# SY_HR08_MCU_POWER_V1_1.net
KiCad netlist of a schematic drawn in Altium Designer
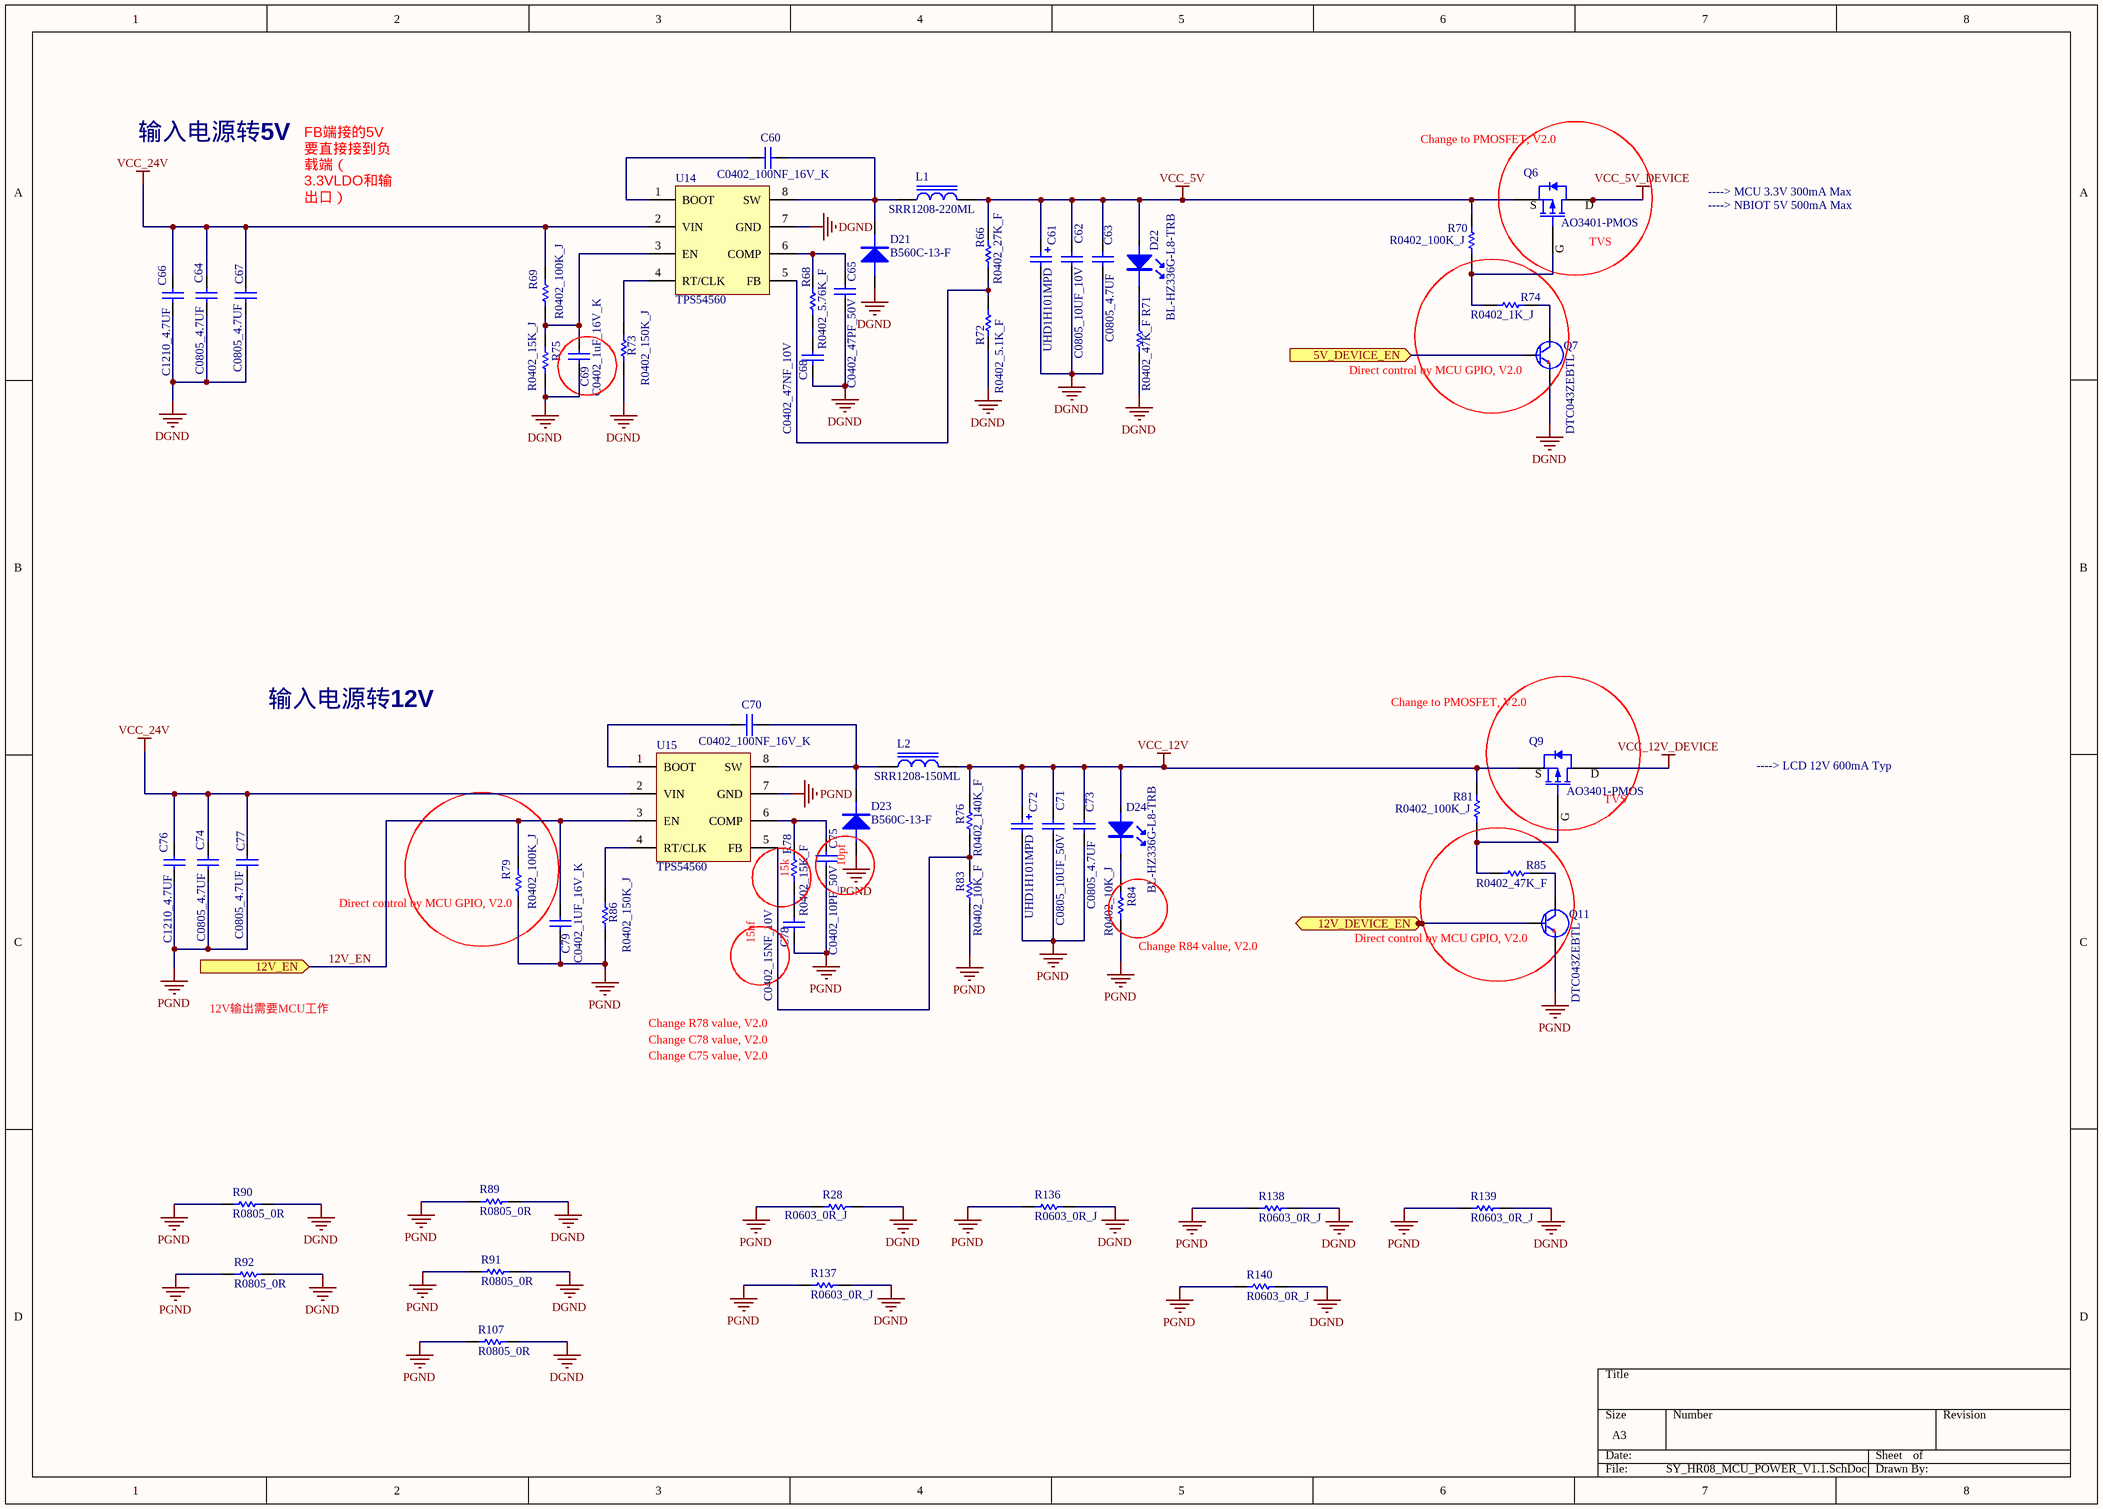
[diagram p0: SY_HR08_MCU_POWER_V1.1.SchDoc]

(export (version "E")
  (design (tool "Eeschema 10.0.6"))
  (components
    (comp (ref "C60")
      (value "C0402_100NF_16V_K")
      (footprint "CAP0402_HQ")
      (description "电容_100nF_0402_X7R_16V_K")
      (libsource (lib "zhangky_sch") (part "C0402_100NF_16V_K"))
    )
    (comp (ref "C61")
      (value "UHD1H101MPD")
      (footprint "UHD1H101MPD")
      (description "铝电解电容_100uF_80115_50V_20%")
      (fields (field (name "MANUFACTURER") "nichicon"))
      (libsource (lib "zhangky_sch") (part "UHD1H101MPD"))
    )
    (comp (ref "C62")
      (value "C0805_10UF_10V")
      (footprint "CAP0805-B")
      (description "电容_10uF_0805_X5R_10V_K")
      (libsource (lib "zhangky_sch") (part "C0805_10UF_10V"))
    )
    (comp (ref "C63")
      (value "C0805_4.7UF")
      (footprint "CAP0805")
      (description "电容_4.7uF_0805_X5R_50V_K")
      (libsource (lib "zhangky_sch") (part "C0805_4.7UF"))
    )
    (comp (ref "C64")
      (value "C0805_4.7UF")
      (footprint "CAP0805")
      (description "电容_4.7uF_0805_X5R_50V_K")
      (libsource (lib "zhangky_sch") (part "C0805_4.7UF"))
    )
    (comp (ref "C65")
      (value "C0402_47PF_50V")
      (footprint "CAP0402_HQ")
      (description "电容47pF(0402-COG-50V-J)")
      (libsource (lib "zhangky_sch") (part "C0402_47PF_50V"))
    )
    (comp (ref "C66")
      (value "C1210_4.7UF")
      (footprint "C1210")
      (description "电容_4.7uF_1210_X7R_50V_K")
      (libsource (lib "zhangky_sch") (part "C1210_4.7UF"))
    )
    (comp (ref "C67")
      (value "C0805_4.7UF")
      (footprint "CAP0805")
      (description "电容_4.7uF_0805_X5R_50V_K")
      (libsource (lib "zhangky_sch") (part "C0805_4.7UF"))
    )
    (comp (ref "C68")
      (value "C0402_47NF_10V")
      (footprint "CAP0402_HQ")
      (description "电容47nF(0402-X7R-10V-K)")
      (libsource (lib "zhangky_sch") (part "C0402_47NF_10V"))
    )
    (comp (ref "C69")
      (value "C0402_1uF_16V_K")
      (footprint "CAP0402_HQ")
      (description "电容_100nF_0402_X7R_16V_K")
      (libsource (lib "zhangky_sch") (part "C0402_100NF_16V_K"))
    )
    (comp (ref "C70")
      (value "C0402_100NF_16V_K")
      (footprint "CAP0402_HQ")
      (description "电容_100nF_0402_X7R_16V_K")
      (libsource (lib "zhangky_sch") (part "C0402_100NF_16V_K"))
    )
    (comp (ref "C71")
      (value "C0805_10UF_50V")
      (footprint "CAP0805-B")
      (description "电容_10uF_0805_X5R_10V_K")
      (libsource (lib "zhangky_sch") (part "C0805_10UF_10V"))
    )
    (comp (ref "C72")
      (value "UHD1H101MPD")
      (footprint "UHD1H101MPD")
      (description "铝电解电容_100uF_80115_50V_20%")
      (fields (field (name "MANUFACTURER") "nichicon"))
      (libsource (lib "zhangky_sch") (part "UHD1H101MPD"))
    )
    (comp (ref "C73")
      (value "C0805_4.7UF")
      (footprint "CAP0805")
      (description "电容_4.7uF_0805_X5R_50V_K")
      (libsource (lib "zhangky_sch") (part "C0805_4.7UF"))
    )
    (comp (ref "C74")
      (value "C0805_4.7UF")
      (footprint "CAP0805")
      (description "电容_4.7uF_0805_X5R_50V_K")
      (libsource (lib "zhangky_sch") (part "C0805_4.7UF"))
    )
    (comp (ref "C75")
      (value "C0402_10PF_50V")
      (footprint "CAP0402_HQ")
      (description "电容47pF(0402-COG-50V-J)")
      (libsource (lib "zhangky_sch") (part "C0402_47PF_50V"))
    )
    (comp (ref "C76")
      (value "C1210_4.7UF")
      (footprint "C1210")
      (description "电容_4.7uF_1210_X7R_50V_K")
      (libsource (lib "zhangky_sch") (part "C1210_4.7UF"))
    )
    (comp (ref "C77")
      (value "C0805_4.7UF")
      (footprint "CAP0805")
      (description "电容_4.7uF_0805_X5R_50V_K")
      (libsource (lib "zhangky_sch") (part "C0805_4.7UF"))
    )
    (comp (ref "C78")
      (value "C0402_15NF_10V")
      (footprint "CAP0402_HQ")
      (description "电容47nF(0402-X7R-10V-K)")
      (libsource (lib "zhangky_sch") (part "C0402_47NF_10V"))
    )
    (comp (ref "C79")
      (value "C0402_1UF_16V_K")
      (footprint "CAP0402_HQ")
      (description "电容_100nF_0402_X7R_16V_K")
      (libsource (lib "zhangky_sch") (part "C0402_100NF_16V_K"))
    )
    (comp (ref "D21")
      (value "B560C-13-F")
      (footprint "B540C-13-F")
      (description "肖特基二极管_5A_SMC")
      (libsource (lib "zhangky_sch") (part "B560C-13-F"))
    )
    (comp (ref "D22")
      (value "BL-HZ336G-L8-TRB")
      (footprint "LED_1.6_0.8_0.4")
      (description "LED_(白色_0603_2.8V)_(HUE仅收5-5,5-6,5-7的标示，CAE仅收含P的标示)")
      (fields (field (name "MANUFACTURER") "Bright(佰鸿)"))
      (libsource (lib "zhangky_sch") (part "BL-HZ336G-L8-TRB"))
    )
    (comp (ref "D23")
      (value "B560C-13-F")
      (footprint "B540C-13-F")
      (description "肖特基二极管_5A_SMC")
      (libsource (lib "zhangky_sch") (part "B560C-13-F"))
    )
    (comp (ref "D24")
      (value "BL-HZ336G-L8-TRB")
      (footprint "LED_1.6_0.8_0.4")
      (description "LED_(白色_0603_2.8V)_(HUE仅收5-5,5-6,5-7的标示，CAE仅收含P的标示)")
      (fields (field (name "MANUFACTURER") "Bright(佰鸿)"))
      (libsource (lib "zhangky_sch") (part "BL-HZ336G-L8-TRB"))
    )
    (comp (ref "L1")
      (value "SRR1208-220ML")
      (footprint "SRR1208")
      (description "功率电感_22uH_12.7*12.7*8.5mm_4A(Irat )_3.5A(Irms)_20%")
      (libsource (lib "zhangky_sch") (part "SRR1208-220ML"))
    )
    (comp (ref "L2")
      (value "SRR1208-150ML")
      (footprint "SRR1208")
      (description "功率电感_15uH_12.7*12.7*8.5mm_4A(Irat )_3.5A(Irms)_20%")
      (libsource (lib "zhangky_sch") (part "SRR1208-150ML"))
    )
    (comp (ref "Q6")
      (value "AO3401-PMOS")
      (footprint "AO3400")
      (libsource (lib "zhangky_sch") (part "AO3401-PMOS"))
    )
    (comp (ref "Q7")
      (value "DTC043ZEBTL")
      (footprint "DTC043ZEBTL$2F$$2F$DTC143ZE$2F$$2F$LDTC143ZET1G")
      (description "NPN三极管_100mA_EMT3F")
      (libsource (lib "zhangky_sch") (part "DTC043ZEBTL"))
    )
    (comp (ref "Q9")
      (value "AO3401-PMOS")
      (footprint "AO3400")
      (libsource (lib "zhangky_sch") (part "AO3401-PMOS"))
    )
    (comp (ref "Q11")
      (value "DTC043ZEBTL")
      (footprint "DTC043ZEBTL$2F$$2F$DTC143ZE$2F$$2F$LDTC143ZET1G")
      (description "NPN三极管_100mA_EMT3F")
      (libsource (lib "zhangky_sch") (part "DTC043ZEBTL"))
    )
    (comp (ref "R28")
      (value "R0603_0R_J")
      (footprint "RES0603-A")
      (description "电阻0R(0603-0.1W-J)")
      (libsource (lib "zhangky_sch") (part "R0603_0R_J"))
    )
    (comp (ref "R66")
      (value "R0402_27K_F")
      (footprint "RES0402_HQ")
      (description "电阻_27K_0402_1/16W_F")
      (libsource (lib "zhangky_sch") (part "R0402_27K_F"))
    )
    (comp (ref "R68")
      (value "R0402_5.76K_F")
      (footprint "RES0402_HQ")
      (description "电阻_5.76K_0402_1/16W_F")
      (libsource (lib "zhangky_sch") (part "R0402_5.76K_F"))
    )
    (comp (ref "R69")
      (value "R0402_100K_J")
      (footprint "RES0402_HQ")
      (description "电阻100K(0402-0.0625W-J)")
      (libsource (lib "zhangky_sch") (part "R0402_100K_J"))
    )
    (comp (ref "R70")
      (value "R0402_100K_J")
      (footprint "RES0402_HQ")
      (description "电阻100K(0402-0.0625W-J)")
      (libsource (lib "zhangky_sch") (part "R0402_100K_J"))
    )
    (comp (ref "R71")
      (value "R0402_47K_F")
      (footprint "RES0402_HQ")
      (description "电阻10K(0402-0.0625W-J)")
      (libsource (lib "zhangky_sch") (part "R0402_10K_J"))
    )
    (comp (ref "R72")
      (value "R0402_5.1K_F")
      (footprint "RES0402_HQ")
      (description "电阻5.1K(0402-0.0625W-J)")
      (libsource (lib "zhangky_sch") (part "R0402_5.1K_F"))
    )
    (comp (ref "R73")
      (value "R0402_150K_J")
      (footprint "RES0402_HQ")
      (description "电阻150K(0402-0.0625w-J)")
      (libsource (lib "zhangky_sch") (part "R0402_150K_J"))
    )
    (comp (ref "R74")
      (value "R0402_1K_J")
      (footprint "RES0402_HQ")
      (description "电阻100K(0402-0.0625W-J)")
      (libsource (lib "zhangky_sch") (part "R0402_100K_J"))
    )
    (comp (ref "R75")
      (value "R0402_15K_J")
      (footprint "RES0402_HQ")
      (description "电阻15K(0402-0.0625W-J)")
      (libsource (lib "zhangky_sch") (part "R0402_15K_J"))
    )
    (comp (ref "R76")
      (value "R0402_140K_F")
      (footprint "RES0402_HQ")
      (description "电阻_140K_0402_1/16W_F")
      (libsource (lib "zhangky_sch") (part "R0402_140K_F"))
    )
    (comp (ref "R78")
      (value "R0402_15K_F")
      (footprint "RES0402_HQ")
      (description "电阻_5.76K_0402_1/16W_F")
      (libsource (lib "zhangky_sch") (part "R0402_5.76K_F"))
    )
    (comp (ref "R79")
      (value "R0402_100K_J")
      (footprint "RES0402_HQ")
      (description "电阻100K(0402-0.0625W-J)")
      (libsource (lib "zhangky_sch") (part "R0402_100K_J"))
    )
    (comp (ref "R81")
      (value "R0402_100K_J")
      (footprint "RES0402_HQ")
      (description "电阻100K(0402-0.0625W-J)")
      (libsource (lib "zhangky_sch") (part "R0402_100K_J"))
    )
    (comp (ref "R83")
      (value "R0402_10K_F")
      (footprint "RES0402_HQ")
      (description "电阻_10K_0402_1/16W_F")
      (libsource (lib "zhangky_sch") (part "R0402_10K_F"))
    )
    (comp (ref "R84")
      (value "R0402_10K_J")
      (footprint "RES0402_HQ")
      (description "电阻15K(0402-0.0625W-J)")
      (libsource (lib "zhangky_sch") (part "R0402_15K_J"))
    )
    (comp (ref "R85")
      (value "R0402_47K_F")
      (footprint "RES0402_HQ")
      (description "电阻100K(0402-0.0625W-J)")
      (libsource (lib "zhangky_sch") (part "R0402_100K_J"))
    )
    (comp (ref "R86")
      (value "R0402_150K_J")
      (footprint "RES0402_HQ")
      (description "电阻150K(0402-0.0625w-J)")
      (libsource (lib "zhangky_sch") (part "R0402_150K_J"))
    )
    (comp (ref "R89")
      (value "R0805_0R")
      (footprint "RES0805")
      (description "电阻0R(0805-0.125W-J)")
      (libsource (lib "zhangky_sch") (part "R0805_0R"))
    )
    (comp (ref "R90")
      (value "R0805_0R")
      (footprint "RES0805")
      (description "电阻0R(0805-0.125W-J)")
      (libsource (lib "zhangky_sch") (part "R0805_0R"))
    )
    (comp (ref "R91")
      (value "R0805_0R")
      (footprint "RES0805")
      (description "电阻0R(0805-0.125W-J)")
      (libsource (lib "zhangky_sch") (part "R0805_0R"))
    )
    (comp (ref "R92")
      (value "R0805_0R")
      (footprint "RES0805")
      (description "电阻0R(0805-0.125W-J)")
      (libsource (lib "zhangky_sch") (part "R0805_0R"))
    )
    (comp (ref "R107")
      (value "R0805_0R")
      (footprint "RES0805")
      (description "电阻0R(0805-0.125W-J)")
      (libsource (lib "zhangky_sch") (part "R0805_0R"))
    )
    (comp (ref "R136")
      (value "R0603_0R_J")
      (footprint "RES0603-A")
      (description "电阻0R(0603-0.1W-J)")
      (libsource (lib "zhangky_sch") (part "R0603_0R_J"))
    )
    (comp (ref "R137")
      (value "R0603_0R_J")
      (footprint "RES0603-A")
      (description "电阻0R(0603-0.1W-J)")
      (libsource (lib "zhangky_sch") (part "R0603_0R_J"))
    )
    (comp (ref "R138")
      (value "R0603_0R_J")
      (footprint "RES0603-A")
      (description "电阻0R(0603-0.1W-J)")
      (libsource (lib "zhangky_sch") (part "R0603_0R_J"))
    )
    (comp (ref "R139")
      (value "R0603_0R_J")
      (footprint "RES0603-A")
      (description "电阻0R(0603-0.1W-J)")
      (libsource (lib "zhangky_sch") (part "R0603_0R_J"))
    )
    (comp (ref "R140")
      (value "R0603_0R_J")
      (footprint "RES0603-A")
      (description "电阻0R(0603-0.1W-J)")
      (libsource (lib "zhangky_sch") (part "R0603_0R_J"))
    )
    (comp (ref "U14")
      (value "TPS54560")
      (footprint "TPS54560")
      (description "Step Down DC-DC Converter")
      (fields (field (name "MANUFACTURER") "TI"))
      (libsource (lib "zhangky_sch") (part "TPS54560"))
    )
    (comp (ref "U15")
      (value "TPS54560")
      (footprint "TPS54560")
      (description "Step Down DC-DC Converter")
      (fields (field (name "MANUFACTURER") "TI"))
      (libsource (lib "zhangky_sch") (part "TPS54560"))
    )
  )
  (nets
    (net (code "1") (name "/5V_DEVICE_EN") (class "Default")
      (node (ref "Q7") (pin "1") (pinfunction "B_1") (pintype "passive"))
    )
    (net (code "2") (name "/12V_DEVICE_EN") (class "Default")
      (node (ref "Q11") (pin "1") (pinfunction "B_1") (pintype "passive"))
    )
    (net (code "3") (name "/12V_EN") (class "Default")
      (node (ref "C79") (pin "2") (pinfunction "2_2") (pintype "passive"))
      (node (ref "R79") (pin "2") (pinfunction "2_2") (pintype "passive"))
      (node (ref "U15") (pin "3") (pinfunction "EN_3") (pintype "passive"))
    )
    (net (code "4") (name "DGND") (class "Default")
      (node (ref "C61") (pin "2") (pinfunction "2_2") (pintype "passive"))
      (node (ref "C62") (pin "1") (pinfunction "1_1") (pintype "passive"))
      (node (ref "C63") (pin "1") (pinfunction "1_1") (pintype "passive"))
      (node (ref "C64") (pin "1") (pinfunction "1_1") (pintype "passive"))
      (node (ref "C65") (pin "1") (pinfunction "1_1") (pintype "passive"))
      (node (ref "C66") (pin "1") (pinfunction "1_1") (pintype "passive"))
      (node (ref "C67") (pin "1") (pinfunction "1_1") (pintype "passive"))
      (node (ref "C68") (pin "1") (pinfunction "1_1") (pintype "passive"))
      (node (ref "C69") (pin "1") (pinfunction "1_1") (pintype "passive"))
      (node (ref "D21") (pin "2") (pinfunction "2_2") (pintype "passive"))
      (node (ref "Q7") (pin "2") (pinfunction "E_2") (pintype "passive"))
      (node (ref "R107") (pin "2") (pinfunction "2_2") (pintype "passive"))
      (node (ref "R136") (pin "2") (pinfunction "2_2") (pintype "passive"))
      (node (ref "R137") (pin "2") (pinfunction "2_2") (pintype "passive"))
      (node (ref "R138") (pin "2") (pinfunction "2_2") (pintype "passive"))
      (node (ref "R139") (pin "2") (pinfunction "2_2") (pintype "passive"))
      (node (ref "R140") (pin "2") (pinfunction "2_2") (pintype "passive"))
      (node (ref "R28") (pin "2") (pinfunction "2_2") (pintype "passive"))
      (node (ref "R71") (pin "1") (pinfunction "1_1") (pintype "passive"))
      (node (ref "R72") (pin "1") (pinfunction "1_1") (pintype "passive"))
      (node (ref "R73") (pin "1") (pinfunction "1_1") (pintype "passive"))
      (node (ref "R75") (pin "1") (pinfunction "1_1") (pintype "passive"))
      (node (ref "R89") (pin "2") (pinfunction "2_2") (pintype "passive"))
      (node (ref "R90") (pin "2") (pinfunction "2_2") (pintype "passive"))
      (node (ref "R91") (pin "2") (pinfunction "2_2") (pintype "passive"))
      (node (ref "R92") (pin "2") (pinfunction "2_2") (pintype "passive"))
      (node (ref "U14") (pin "7") (pinfunction "GND_7") (pintype "passive"))
    )
    (net (code "5") (name "Net-(C68-Pad2)") (class "Default")
      (node (ref "C68") (pin "2") (pinfunction "2_2") (pintype "passive"))
      (node (ref "R68") (pin "1") (pinfunction "1_1") (pintype "passive"))
    )
    (net (code "6") (name "Net-(C78-Pad2)") (class "Default")
      (node (ref "C78") (pin "2") (pinfunction "2_2") (pintype "passive"))
      (node (ref "R78") (pin "1") (pinfunction "1_1") (pintype "passive"))
    )
    (net (code "7") (name "Net-(D22-Pad1)") (class "Default")
      (node (ref "D22") (pin "1") (pinfunction "1_1") (pintype "passive"))
      (node (ref "R71") (pin "2") (pinfunction "2_2") (pintype "passive"))
    )
    (net (code "8") (name "Net-(D24-Pad1)") (class "Default")
      (node (ref "D24") (pin "1") (pinfunction "1_1") (pintype "passive"))
      (node (ref "R84") (pin "2") (pinfunction "2_2") (pintype "passive"))
    )
    (net (code "9") (name "Net-(Q6-G)") (class "Default")
      (node (ref "Q6") (pin "1") (pinfunction "G_1") (pintype "passive"))
      (node (ref "R70") (pin "1") (pinfunction "1_1") (pintype "passive"))
      (node (ref "R74") (pin "2") (pinfunction "2_2") (pintype "passive"))
    )
    (net (code "10") (name "Net-(Q7-C)") (class "Default")
      (node (ref "Q7") (pin "3") (pinfunction "C_3") (pintype "passive"))
      (node (ref "R74") (pin "1") (pinfunction "1_1") (pintype "passive"))
    )
    (net (code "11") (name "Net-(Q9-G)") (class "Default")
      (node (ref "Q9") (pin "1") (pinfunction "G_1") (pintype "passive"))
      (node (ref "R81") (pin "1") (pinfunction "1_1") (pintype "passive"))
      (node (ref "R85") (pin "2") (pinfunction "2_2") (pintype "passive"))
    )
    (net (code "12") (name "Net-(Q11-C)") (class "Default")
      (node (ref "Q11") (pin "3") (pinfunction "C_3") (pintype "passive"))
      (node (ref "R85") (pin "1") (pinfunction "1_1") (pintype "passive"))
    )
    (net (code "13") (name "Net-(U14-BOOT)") (class "Default")
      (node (ref "C60") (pin "2") (pinfunction "2_2") (pintype "passive"))
      (node (ref "U14") (pin "1") (pinfunction "BOOT_1") (pintype "passive"))
    )
    (net (code "14") (name "Net-(U14-COMP)") (class "Default")
      (node (ref "C65") (pin "2") (pinfunction "2_2") (pintype "passive"))
      (node (ref "R68") (pin "2") (pinfunction "2_2") (pintype "passive"))
      (node (ref "U14") (pin "6") (pinfunction "COMP_6") (pintype "passive"))
    )
    (net (code "15") (name "Net-(U14-EN)") (class "Default")
      (node (ref "C69") (pin "2") (pinfunction "2_2") (pintype "passive"))
      (node (ref "R69") (pin "1") (pinfunction "1_1") (pintype "passive"))
      (node (ref "R75") (pin "2") (pinfunction "2_2") (pintype "passive"))
      (node (ref "U14") (pin "3") (pinfunction "EN_3") (pintype "passive"))
    )
    (net (code "16") (name "Net-(U14-FB)") (class "Default")
      (node (ref "R66") (pin "1") (pinfunction "1_1") (pintype "passive"))
      (node (ref "R72") (pin "2") (pinfunction "2_2") (pintype "passive"))
      (node (ref "U14") (pin "5") (pinfunction "FB_5") (pintype "passive"))
    )
    (net (code "17") (name "Net-(U14-RT{slash}CLK)") (class "Default")
      (node (ref "R73") (pin "2") (pinfunction "2_2") (pintype "passive"))
      (node (ref "U14") (pin "4") (pinfunction "RT/CLK_4") (pintype "passive"))
    )
    (net (code "18") (name "Net-(U14-SW)") (class "Default")
      (node (ref "C60") (pin "1") (pinfunction "1_1") (pintype "passive"))
      (node (ref "D21") (pin "1") (pinfunction "1_1") (pintype "passive"))
      (node (ref "L1") (pin "1") (pintype "passive"))
      (node (ref "U14") (pin "8") (pinfunction "SW_8") (pintype "passive"))
    )
    (net (code "19") (name "Net-(U15-BOOT)") (class "Default")
      (node (ref "C70") (pin "2") (pinfunction "2_2") (pintype "passive"))
      (node (ref "U15") (pin "1") (pinfunction "BOOT_1") (pintype "passive"))
    )
    (net (code "20") (name "Net-(U15-COMP)") (class "Default")
      (node (ref "C75") (pin "2") (pinfunction "2_2") (pintype "passive"))
      (node (ref "R78") (pin "2") (pinfunction "2_2") (pintype "passive"))
      (node (ref "U15") (pin "6") (pinfunction "COMP_6") (pintype "passive"))
    )
    (net (code "21") (name "Net-(U15-FB)") (class "Default")
      (node (ref "R76") (pin "1") (pinfunction "1_1") (pintype "passive"))
      (node (ref "R83") (pin "2") (pinfunction "2_2") (pintype "passive"))
      (node (ref "U15") (pin "5") (pinfunction "FB_5") (pintype "passive"))
    )
    (net (code "22") (name "Net-(U15-RT{slash}CLK)") (class "Default")
      (node (ref "R86") (pin "2") (pinfunction "2_2") (pintype "passive"))
      (node (ref "U15") (pin "4") (pinfunction "RT/CLK_4") (pintype "passive"))
    )
    (net (code "23") (name "Net-(U15-SW)") (class "Default")
      (node (ref "C70") (pin "1") (pinfunction "1_1") (pintype "passive"))
      (node (ref "D23") (pin "1") (pinfunction "1_1") (pintype "passive"))
      (node (ref "L2") (pin "1") (pintype "passive"))
      (node (ref "U15") (pin "8") (pinfunction "SW_8") (pintype "passive"))
    )
    (net (code "24") (name "PGND") (class "Default")
      (node (ref "C71") (pin "1") (pinfunction "1_1") (pintype "passive"))
      (node (ref "C72") (pin "2") (pinfunction "2_2") (pintype "passive"))
      (node (ref "C73") (pin "1") (pinfunction "1_1") (pintype "passive"))
      (node (ref "C74") (pin "1") (pinfunction "1_1") (pintype "passive"))
      (node (ref "C75") (pin "1") (pinfunction "1_1") (pintype "passive"))
      (node (ref "C76") (pin "1") (pinfunction "1_1") (pintype "passive"))
      (node (ref "C77") (pin "1") (pinfunction "1_1") (pintype "passive"))
      (node (ref "C78") (pin "1") (pinfunction "1_1") (pintype "passive"))
      (node (ref "C79") (pin "1") (pinfunction "1_1") (pintype "passive"))
      (node (ref "D23") (pin "2") (pinfunction "2_2") (pintype "passive"))
      (node (ref "Q11") (pin "2") (pinfunction "E_2") (pintype "passive"))
      (node (ref "R107") (pin "1") (pinfunction "1_1") (pintype "passive"))
      (node (ref "R136") (pin "1") (pinfunction "1_1") (pintype "passive"))
      (node (ref "R137") (pin "1") (pinfunction "1_1") (pintype "passive"))
      (node (ref "R138") (pin "1") (pinfunction "1_1") (pintype "passive"))
      (node (ref "R139") (pin "1") (pinfunction "1_1") (pintype "passive"))
      (node (ref "R140") (pin "1") (pinfunction "1_1") (pintype "passive"))
      (node (ref "R28") (pin "1") (pinfunction "1_1") (pintype "passive"))
      (node (ref "R79") (pin "1") (pinfunction "1_1") (pintype "passive"))
      (node (ref "R83") (pin "1") (pinfunction "1_1") (pintype "passive"))
      (node (ref "R84") (pin "1") (pinfunction "1_1") (pintype "passive"))
      (node (ref "R86") (pin "1") (pinfunction "1_1") (pintype "passive"))
      (node (ref "R89") (pin "1") (pinfunction "1_1") (pintype "passive"))
      (node (ref "R90") (pin "1") (pinfunction "1_1") (pintype "passive"))
      (node (ref "R91") (pin "1") (pinfunction "1_1") (pintype "passive"))
      (node (ref "R92") (pin "1") (pinfunction "1_1") (pintype "passive"))
      (node (ref "U15") (pin "7") (pinfunction "GND_7") (pintype "passive"))
    )
    (net (code "25") (name "VCC_5V") (class "Default")
      (node (ref "C61") (pin "1") (pinfunction "1_1") (pintype "passive"))
      (node (ref "C62") (pin "2") (pinfunction "2_2") (pintype "passive"))
      (node (ref "C63") (pin "2") (pinfunction "2_2") (pintype "passive"))
      (node (ref "D22") (pin "2") (pinfunction "2_2") (pintype "passive"))
      (node (ref "L1") (pin "2") (pintype "passive"))
      (node (ref "Q6") (pin "2") (pinfunction "S_2") (pintype "passive"))
      (node (ref "R66") (pin "2") (pinfunction "2_2") (pintype "passive"))
      (node (ref "R70") (pin "2") (pinfunction "2_2") (pintype "passive"))
    )
    (net (code "26") (name "VCC_5V_DEVICE") (class "Default")
      (node (ref "Q6") (pin "3") (pinfunction "D_3") (pintype "passive"))
    )
    (net (code "27") (name "VCC_12V") (class "Default")
      (node (ref "C71") (pin "2") (pinfunction "2_2") (pintype "passive"))
      (node (ref "C72") (pin "1") (pinfunction "1_1") (pintype "passive"))
      (node (ref "C73") (pin "2") (pinfunction "2_2") (pintype "passive"))
      (node (ref "D24") (pin "2") (pinfunction "2_2") (pintype "passive"))
      (node (ref "L2") (pin "2") (pintype "passive"))
      (node (ref "Q9") (pin "2") (pinfunction "S_2") (pintype "passive"))
      (node (ref "R76") (pin "2") (pinfunction "2_2") (pintype "passive"))
      (node (ref "R81") (pin "2") (pinfunction "2_2") (pintype "passive"))
    )
    (net (code "28") (name "VCC_12V_DEVICE") (class "Default")
      (node (ref "Q9") (pin "3") (pinfunction "D_3") (pintype "passive"))
    )
    (net (code "29") (name "VCC_24V") (class "Default")
      (node (ref "C64") (pin "2") (pinfunction "2_2") (pintype "passive"))
      (node (ref "C66") (pin "2") (pinfunction "2_2") (pintype "passive"))
      (node (ref "C67") (pin "2") (pinfunction "2_2") (pintype "passive"))
      (node (ref "C74") (pin "2") (pinfunction "2_2") (pintype "passive"))
      (node (ref "C76") (pin "2") (pinfunction "2_2") (pintype "passive"))
      (node (ref "C77") (pin "2") (pinfunction "2_2") (pintype "passive"))
      (node (ref "R69") (pin "2") (pinfunction "2_2") (pintype "passive"))
      (node (ref "U14") (pin "2") (pinfunction "VIN_2") (pintype "passive"))
      (node (ref "U15") (pin "2") (pinfunction "VIN_2") (pintype "passive"))
    )
  )
)
